# design.net
KiCad netlist of a schematic drawn in Altium Designer
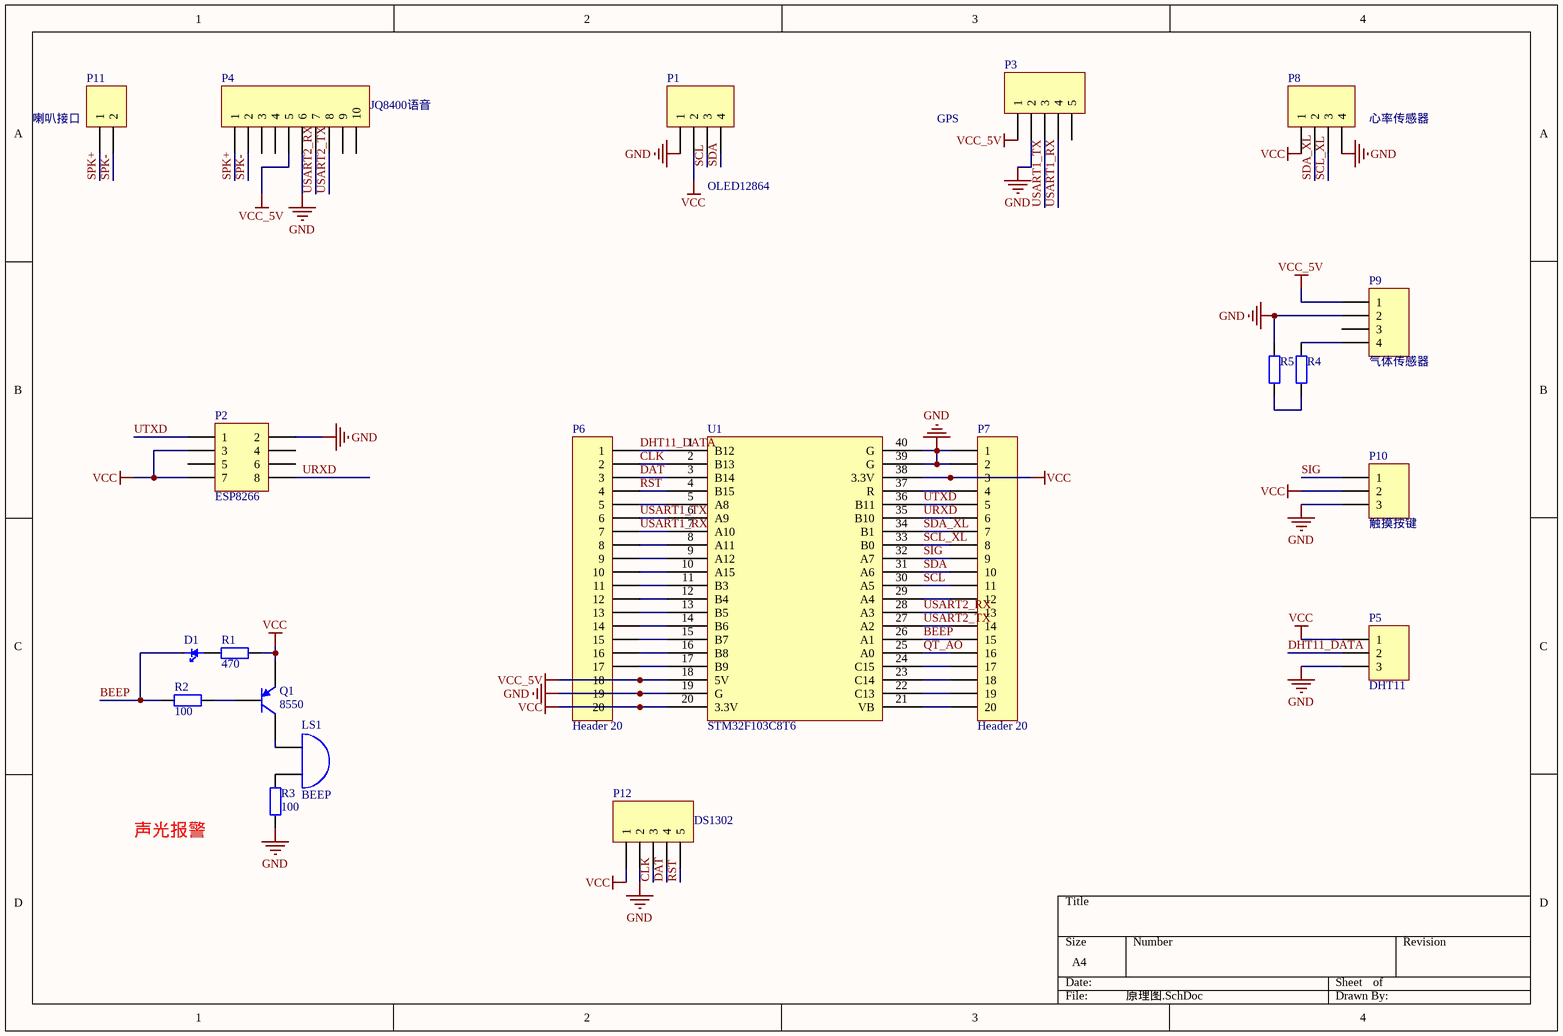
[diagram p0: 原理图.SchDoc]

(export (version "E")
  (design (tool "Eeschema 10.0.6"))
  (components
    (comp (ref "D1") (value "W") (footprint "LC-0805_LED_S1") (libsource (lib "个人") (part "LED")))
    (comp (ref "LS1")
      (value "BEEP")
      (footprint "HDR1X4")
      (description "Electrical Bell")
      (fields (field (name "PUBLISHER") "Altium Limited"))
      (libsource (lib "Miscellaneous Devices") (part "Bell"))
    )
    (comp (ref "P1")
      (value "OLED12864")
      (footprint "HDR1X4")
      (description "Header, 4-Pin")
      (fields (field (name "PUBLISHER") "Altium Limited"))
      (libsource (lib "Miscellaneous Connectors") (part "Header 4"))
    )
    (comp (ref "P2")
      (value "ESP8266")
      (footprint "HDR2X4")
      (description "Header, 4-Pin, Dual row")
      (fields (field (name "PUBLISHER") "Altium Limited"))
      (libsource (lib "Miscellaneous Connectors") (part "Header 4X2"))
    )
    (comp (ref "P3")
      (value "GPS")
      (footprint "HDR1X5")
      (description "Header, 5-Pin")
      (fields (field (name "PUBLISHER") "Altium Limited"))
      (libsource (lib "Miscellaneous Connectors") (part "Header 5"))
    )
    (comp (ref "P4")
      (value "JQ8400语音")
      (footprint "HDR1X10")
      (description "Header, 10-Pin")
      (fields (field (name "PUBLISHER") "Altium Limited"))
      (libsource (lib "Miscellaneous Connectors") (part "Header 10"))
    )
    (comp (ref "P5")
      (value "DHT11")
      (footprint "HDR1X3")
      (description "Header, 3-Pin")
      (fields (field (name "PUBLISHER") "Altium Limited"))
      (libsource (lib "Miscellaneous Connectors") (part "Header 3"))
    )
    (comp (ref "P6")
      (value "Header 20")
      (footprint "HDR1X20")
      (description "Header, 20-Pin")
      (fields (field (name "PUBLISHER") "Altium Limited"))
      (libsource (lib "") (part "Header 20_1"))
    )
    (comp (ref "P7")
      (value "Header 20")
      (footprint "HDR1X20")
      (description "Header, 20-Pin")
      (fields (field (name "PUBLISHER") "Altium Limited"))
      (libsource (lib "Miscellaneous Connectors") (part "Header 20"))
    )
    (comp (ref "P8")
      (value "心率传感器")
      (footprint "HDR1X4")
      (description "Header, 4-Pin")
      (fields (field (name "PUBLISHER") "Altium Limited"))
      (libsource (lib "Miscellaneous Connectors") (part "Header 4"))
    )
    (comp (ref "P9")
      (value "气体传感器")
      (footprint "HDR1X4")
      (description "Header, 4-Pin")
      (fields (field (name "PUBLISHER") "Altium Limited"))
      (libsource (lib "") (part "Header 4_1"))
    )
    (comp (ref "P10")
      (value "触摸按键")
      (footprint "HDR1X3")
      (description "Header, 3-Pin")
      (fields (field (name "PUBLISHER") "Altium Limited"))
      (libsource (lib "Miscellaneous Connectors") (part "Header 3"))
    )
    (comp (ref "P11")
      (value "喇叭接口")
      (footprint "HDR1X2")
      (description "Header, 2-Pin")
      (fields (field (name "PUBLISHER") "Altium Limited"))
      (libsource (lib "Miscellaneous Connectors") (part "Header 2"))
    )
    (comp (ref "P12")
      (value "DS1302")
      (footprint "HDR1X5")
      (description "Header, 5-Pin")
      (fields (field (name "PUBLISHER") "Altium Limited"))
      (libsource (lib "Miscellaneous Connectors") (part "Header 5"))
    )
    (comp (ref "Q1")
      (value "8550")
      (footprint "SOT-23 MOS")
      (description "PNP General Purpose Amplifier")
      (fields (field (name "PUBLISHER") "Altium Limited"))
      (libsource (lib "Miscellaneous Devices") (part "2N3906"))
    )
    (comp (ref "R1")
      (value "470")
      (footprint "0805")
      (description "Resistor")
      (fields (field (name "Comment") "Res2") (field (name "PUBLISHER") "Altium Limited"))
      (libsource (lib "Miscellaneous Devices") (part "Res2"))
    )
    (comp (ref "R2")
      (value "100")
      (footprint "0805")
      (description "Resistor")
      (fields (field (name "Comment") "Res2") (field (name "PUBLISHER") "Altium Limited"))
      (libsource (lib "Miscellaneous Devices") (part "Res2"))
    )
    (comp (ref "R3")
      (value "100")
      (footprint "0805")
      (description "Resistor")
      (fields (field (name "Comment") "Res2") (field (name "PUBLISHER") "Altium Limited"))
      (libsource (lib "") (part "Res2_2"))
    )
    (comp (ref "R4")
      (value "Res2")
      (footprint "0805")
      (description "Resistor")
      (fields (field (name "PUBLISHER") "Altium Limited"))
      (libsource (lib "") (part "Res2_1"))
    )
    (comp (ref "R5")
      (value "Res2")
      (footprint "0805")
      (description "Resistor")
      (fields (field (name "PUBLISHER") "Altium Limited"))
      (libsource (lib "") (part "Res2_1"))
    )
    (comp (ref "U1")
      (value "STM32F103C8T6")
      (footprint "STM32F103C8T6_HXB")
      (libsource (lib "stm32f103c8t6最小系统板") (part "Component_1"))
    )
  )
  (nets
    (net (code "1") (name "/BEEP") (class "Default")
      (node (ref "D1") (pin "K") (pinfunction "K_K") (pintype "passive"))
      (node (ref "P7") (pin "15") (pinfunction "15_15") (pintype "passive"))
      (node (ref "R2") (pin "2") (pinfunction "2_2") (pintype "passive"))
      (node (ref "U1") (pin "26") (pinfunction "A1_26") (pintype "passive"))
    )
    (net (code "2") (name "/CLK") (class "Default")
      (node (ref "P12") (pin "3") (pinfunction "3_3") (pintype "passive"))
      (node (ref "P6") (pin "2") (pinfunction "2_2") (pintype "passive"))
      (node (ref "U1") (pin "2") (pinfunction "B13_2") (pintype "passive"))
    )
    (net (code "3") (name "/DAT") (class "Default")
      (node (ref "P12") (pin "4") (pinfunction "4_4") (pintype "passive"))
      (node (ref "P6") (pin "3") (pinfunction "3_3") (pintype "passive"))
      (node (ref "U1") (pin "3") (pinfunction "B14_3") (pintype "passive"))
    )
    (net (code "4") (name "/DHT11_DATA") (class "Default")
      (node (ref "P5") (pin "2") (pinfunction "2_2") (pintype "passive"))
      (node (ref "P6") (pin "1") (pinfunction "1_1") (pintype "passive"))
      (node (ref "U1") (pin "1") (pinfunction "B12_1") (pintype "passive"))
    )
    (net (code "5") (name "/QT_AO") (class "Default")
      (node (ref "P7") (pin "16") (pinfunction "16_16") (pintype "passive"))
      (node (ref "U1") (pin "25") (pinfunction "A0_25") (pintype "passive"))
    )
    (net (code "6") (name "/RST") (class "Default")
      (node (ref "P12") (pin "5") (pinfunction "5_5") (pintype "passive"))
      (node (ref "P6") (pin "4") (pinfunction "4_4") (pintype "passive"))
      (node (ref "U1") (pin "4") (pinfunction "B15_4") (pintype "passive"))
    )
    (net (code "7") (name "/SCL") (class "Default")
      (node (ref "P1") (pin "3") (pinfunction "3_3") (pintype "passive"))
      (node (ref "P7") (pin "11") (pinfunction "11_11") (pintype "passive"))
      (node (ref "U1") (pin "30") (pinfunction "A5_30") (pintype "passive"))
    )
    (net (code "8") (name "/SCL_XL") (class "Default")
      (node (ref "P7") (pin "8") (pinfunction "8_8") (pintype "passive"))
      (node (ref "P8") (pin "3") (pinfunction "3_3") (pintype "passive"))
      (node (ref "U1") (pin "33") (pinfunction "B0_33") (pintype "passive"))
    )
    (net (code "9") (name "/SDA") (class "Default")
      (node (ref "P1") (pin "4") (pinfunction "4_4") (pintype "passive"))
      (node (ref "P7") (pin "10") (pinfunction "10_10") (pintype "passive"))
      (node (ref "U1") (pin "31") (pinfunction "A6_31") (pintype "passive"))
    )
    (net (code "10") (name "/SDA_XL") (class "Default")
      (node (ref "P7") (pin "7") (pinfunction "7_7") (pintype "passive"))
      (node (ref "P8") (pin "2") (pinfunction "2_2") (pintype "passive"))
      (node (ref "U1") (pin "34") (pinfunction "B1_34") (pintype "passive"))
    )
    (net (code "11") (name "/SIG") (class "Default")
      (node (ref "P10") (pin "1") (pinfunction "1_1") (pintype "passive"))
      (node (ref "P7") (pin "9") (pinfunction "9_9") (pintype "passive"))
      (node (ref "U1") (pin "32") (pinfunction "A7_32") (pintype "passive"))
    )
    (net (code "12") (name "/SPK+") (class "Default")
      (node (ref "P11") (pin "1") (pinfunction "1_1") (pintype "passive"))
      (node (ref "P4") (pin "1") (pinfunction "1_1") (pintype "passive"))
    )
    (net (code "13") (name "/SPK-") (class "Default")
      (node (ref "P11") (pin "2") (pinfunction "2_2") (pintype "passive"))
      (node (ref "P4") (pin "2") (pinfunction "2_2") (pintype "passive"))
    )
    (net (code "14") (name "/URXD") (class "Default")
      (node (ref "P2") (pin "8") (pinfunction "8_8") (pintype "passive"))
      (node (ref "P7") (pin "6") (pinfunction "6_6") (pintype "passive"))
      (node (ref "U1") (pin "35") (pinfunction "B10_35") (pintype "passive"))
    )
    (net (code "15") (name "/USART1_RX") (class "Default")
      (node (ref "P3") (pin "4") (pinfunction "4_4") (pintype "passive"))
      (node (ref "P6") (pin "7") (pinfunction "7_7") (pintype "passive"))
      (node (ref "U1") (pin "7") (pinfunction "A10_7") (pintype "passive"))
    )
    (net (code "16") (name "/USART1_TX") (class "Default")
      (node (ref "P3") (pin "3") (pinfunction "3_3") (pintype "passive"))
      (node (ref "P6") (pin "6") (pinfunction "6_6") (pintype "passive"))
      (node (ref "U1") (pin "6") (pinfunction "A9_6") (pintype "passive"))
    )
    (net (code "17") (name "/USART2_RX") (class "Default")
      (node (ref "P4") (pin "7") (pinfunction "7_7") (pintype "passive"))
      (node (ref "P7") (pin "13") (pinfunction "13_13") (pintype "passive"))
      (node (ref "U1") (pin "28") (pinfunction "A3_28") (pintype "passive"))
    )
    (net (code "18") (name "/USART2_TX") (class "Default")
      (node (ref "P4") (pin "8") (pinfunction "8_8") (pintype "passive"))
      (node (ref "P7") (pin "14") (pinfunction "14_14") (pintype "passive"))
      (node (ref "U1") (pin "27") (pinfunction "A2_27") (pintype "passive"))
    )
    (net (code "19") (name "/UTXD") (class "Default")
      (node (ref "P2") (pin "1") (pinfunction "1_1") (pintype "passive"))
      (node (ref "P7") (pin "5") (pinfunction "5_5") (pintype "passive"))
      (node (ref "U1") (pin "36") (pinfunction "B11_36") (pintype "passive"))
    )
    (net (code "20") (name "GND") (class "Default")
      (node (ref "P1") (pin "1") (pinfunction "1_1") (pintype "passive"))
      (node (ref "P10") (pin "3") (pinfunction "3_3") (pintype "passive"))
      (node (ref "P12") (pin "2") (pinfunction "2_2") (pintype "passive"))
      (node (ref "P2") (pin "2") (pinfunction "2_2") (pintype "passive"))
      (node (ref "P3") (pin "2") (pinfunction "2_2") (pintype "passive"))
      (node (ref "P4") (pin "6") (pinfunction "6_6") (pintype "passive"))
      (node (ref "P5") (pin "3") (pinfunction "3_3") (pintype "passive"))
      (node (ref "P6") (pin "19") (pinfunction "19_19") (pintype "passive"))
      (node (ref "P7") (pin "1") (pinfunction "1_1") (pintype "passive"))
      (node (ref "P7") (pin "2") (pinfunction "2_2") (pintype "passive"))
      (node (ref "P8") (pin "4") (pinfunction "4_4") (pintype "passive"))
      (node (ref "P9") (pin "2") (pinfunction "2_2") (pintype "passive"))
      (node (ref "R3") (pin "1") (pinfunction "1_1") (pintype "passive"))
      (node (ref "R5") (pin "1") (pinfunction "1_1") (pintype "passive"))
      (node (ref "U1") (pin "19") (pinfunction "G_19") (pintype "passive"))
      (node (ref "U1") (pin "39") (pinfunction "G_39") (pintype "passive"))
      (node (ref "U1") (pin "40") (pinfunction "G_40") (pintype "passive"))
    )
    (net (code "21") (name "Net-(D1-PadA)") (class "Default")
      (node (ref "D1") (pin "A") (pinfunction "A_A") (pintype "passive"))
      (node (ref "R1") (pin "2") (pinfunction "2_2") (pintype "passive"))
    )
    (net (code "22") (name "Net-(LS1-A)") (class "Default")
      (node (ref "LS1") (pin "1") (pinfunction "A_1") (pintype "passive"))
      (node (ref "Q1") (pin "3") (pinfunction "C_3") (pintype "passive"))
    )
    (net (code "23") (name "Net-(LS1-B)") (class "Default")
      (node (ref "LS1") (pin "2") (pinfunction "B_2") (pintype "passive"))
      (node (ref "R3") (pin "2") (pinfunction "2_2") (pintype "passive"))
    )
    (net (code "24") (name "Net-(P9-Pad4)") (class "Default")
      (node (ref "P9") (pin "4") (pinfunction "4_4") (pintype "passive"))
      (node (ref "R4") (pin "1") (pinfunction "1_1") (pintype "passive"))
    )
    (net (code "25") (name "Net-(Q1-B)") (class "Default")
      (node (ref "Q1") (pin "2") (pinfunction "B_2") (pintype "passive"))
      (node (ref "R2") (pin "1") (pinfunction "1_1") (pintype "passive"))
    )
    (net (code "26") (name "Net-(R4-Pad2)") (class "Default")
      (node (ref "R4") (pin "2") (pinfunction "2_2") (pintype "passive"))
      (node (ref "R5") (pin "2") (pinfunction "2_2") (pintype "passive"))
    )
    (net (code "27") (name "Net-(U1-A4)") (class "Default")
      (node (ref "P7") (pin "12") (pinfunction "12_12") (pintype "passive"))
      (node (ref "U1") (pin "29") (pinfunction "A4_29") (pintype "passive"))
    )
    (net (code "28") (name "Net-(U1-A8)") (class "Default")
      (node (ref "P6") (pin "5") (pinfunction "5_5") (pintype "passive"))
      (node (ref "U1") (pin "5") (pinfunction "A8_5") (pintype "passive"))
    )
    (net (code "29") (name "Net-(U1-A11)") (class "Default")
      (node (ref "P6") (pin "8") (pinfunction "8_8") (pintype "passive"))
      (node (ref "U1") (pin "8") (pinfunction "A11_8") (pintype "passive"))
    )
    (net (code "30") (name "Net-(U1-A12)") (class "Default")
      (node (ref "P6") (pin "9") (pinfunction "9_9") (pintype "passive"))
      (node (ref "U1") (pin "9") (pinfunction "A12_9") (pintype "passive"))
    )
    (net (code "31") (name "Net-(U1-A15)") (class "Default")
      (node (ref "P6") (pin "10") (pinfunction "10_10") (pintype "passive"))
      (node (ref "U1") (pin "10") (pinfunction "A15_10") (pintype "passive"))
    )
    (net (code "32") (name "Net-(U1-B3)") (class "Default")
      (node (ref "P6") (pin "11") (pinfunction "11_11") (pintype "passive"))
      (node (ref "U1") (pin "11") (pinfunction "B3_11") (pintype "passive"))
    )
    (net (code "33") (name "Net-(U1-B4)") (class "Default")
      (node (ref "P6") (pin "12") (pinfunction "12_12") (pintype "passive"))
      (node (ref "U1") (pin "12") (pinfunction "B4_12") (pintype "passive"))
    )
    (net (code "34") (name "Net-(U1-B5)") (class "Default")
      (node (ref "P6") (pin "13") (pinfunction "13_13") (pintype "passive"))
      (node (ref "U1") (pin "13") (pinfunction "B5_13") (pintype "passive"))
    )
    (net (code "35") (name "Net-(U1-B6)") (class "Default")
      (node (ref "P6") (pin "14") (pinfunction "14_14") (pintype "passive"))
      (node (ref "U1") (pin "14") (pinfunction "B6_14") (pintype "passive"))
    )
    (net (code "36") (name "Net-(U1-B7)") (class "Default")
      (node (ref "P6") (pin "15") (pinfunction "15_15") (pintype "passive"))
      (node (ref "U1") (pin "15") (pinfunction "B7_15") (pintype "passive"))
    )
    (net (code "37") (name "Net-(U1-B8)") (class "Default")
      (node (ref "P6") (pin "16") (pinfunction "16_16") (pintype "passive"))
      (node (ref "U1") (pin "16") (pinfunction "B8_16") (pintype "passive"))
    )
    (net (code "38") (name "Net-(U1-B9)") (class "Default")
      (node (ref "P6") (pin "17") (pinfunction "17_17") (pintype "passive"))
      (node (ref "U1") (pin "17") (pinfunction "B9_17") (pintype "passive"))
    )
    (net (code "39") (name "Net-(U1-C13)") (class "Default")
      (node (ref "P7") (pin "19") (pinfunction "19_19") (pintype "passive"))
      (node (ref "U1") (pin "22") (pinfunction "C13_22") (pintype "passive"))
    )
    (net (code "40") (name "Net-(U1-C14)") (class "Default")
      (node (ref "P7") (pin "18") (pinfunction "18_18") (pintype "passive"))
      (node (ref "U1") (pin "23") (pinfunction "C14_23") (pintype "passive"))
    )
    (net (code "41") (name "Net-(U1-C15)") (class "Default")
      (node (ref "P7") (pin "17") (pinfunction "17_17") (pintype "passive"))
      (node (ref "U1") (pin "24") (pinfunction "C15_24") (pintype "passive"))
    )
    (net (code "42") (name "Net-(U1-R)") (class "Default")
      (node (ref "P7") (pin "4") (pinfunction "4_4") (pintype "passive"))
      (node (ref "U1") (pin "37") (pinfunction "R_37") (pintype "passive"))
    )
    (net (code "43") (name "Net-(U1-VB)") (class "Default")
      (node (ref "P7") (pin "20") (pinfunction "20_20") (pintype "passive"))
      (node (ref "U1") (pin "21") (pinfunction "VB_21") (pintype "passive"))
    )
    (net (code "44") (name "VCC") (class "Default")
      (node (ref "P1") (pin "2") (pinfunction "2_2") (pintype "passive"))
      (node (ref "P10") (pin "2") (pinfunction "2_2") (pintype "passive"))
      (node (ref "P12") (pin "1") (pinfunction "1_1") (pintype "passive"))
      (node (ref "P2") (pin "3") (pinfunction "3_3") (pintype "passive"))
      (node (ref "P2") (pin "7") (pinfunction "7_7") (pintype "passive"))
      (node (ref "P5") (pin "1") (pinfunction "1_1") (pintype "passive"))
      (node (ref "P6") (pin "20") (pinfunction "20_20") (pintype "passive"))
      (node (ref "P7") (pin "3") (pinfunction "3_3") (pintype "passive"))
      (node (ref "P8") (pin "1") (pinfunction "1_1") (pintype "passive"))
      (node (ref "Q1") (pin "1") (pinfunction "E_1") (pintype "passive"))
      (node (ref "R1") (pin "1") (pinfunction "1_1") (pintype "passive"))
      (node (ref "U1") (pin "20") (pinfunction "3.3V_20") (pintype "passive"))
      (node (ref "U1") (pin "38") (pinfunction "3.3V_38") (pintype "passive"))
    )
    (net (code "45") (name "VCC_5V") (class "Default")
      (node (ref "P3") (pin "1") (pinfunction "1_1") (pintype "passive"))
      (node (ref "P4") (pin "5") (pinfunction "5_5") (pintype "passive"))
      (node (ref "P6") (pin "18") (pinfunction "18_18") (pintype "passive"))
      (node (ref "P9") (pin "1") (pinfunction "1_1") (pintype "passive"))
      (node (ref "U1") (pin "18") (pinfunction "5V_18") (pintype "passive"))
    )
    (net (code "46") (name "unconnected-(P2-Pad4)") (class "Default")
      (node (ref "P2") (pin "4") (pinfunction "4_4") (pintype "passive"))
    )
    (net (code "47") (name "unconnected-(P2-Pad5)") (class "Default")
      (node (ref "P2") (pin "5") (pinfunction "5_5") (pintype "passive"))
    )
    (net (code "48") (name "unconnected-(P2-Pad6)") (class "Default")
      (node (ref "P2") (pin "6") (pinfunction "6_6") (pintype "passive"))
    )
    (net (code "49") (name "unconnected-(P3-Pad5)") (class "Default")
      (node (ref "P3") (pin "5") (pinfunction "5_5") (pintype "passive"))
    )
    (net (code "50") (name "unconnected-(P4-Pad3)") (class "Default")
      (node (ref "P4") (pin "3") (pinfunction "3_3") (pintype "passive"))
    )
    (net (code "51") (name "unconnected-(P4-Pad4)") (class "Default")
      (node (ref "P4") (pin "4") (pinfunction "4_4") (pintype "passive"))
    )
    (net (code "52") (name "unconnected-(P4-Pad9)") (class "Default")
      (node (ref "P4") (pin "9") (pinfunction "9_9") (pintype "passive"))
    )
    (net (code "53") (name "unconnected-(P4-Pad10)") (class "Default")
      (node (ref "P4") (pin "10") (pinfunction "10_10") (pintype "passive"))
    )
    (net (code "54") (name "unconnected-(P9-Pad3)") (class "Default")
      (node (ref "P9") (pin "3") (pinfunction "3_3") (pintype "passive"))
    )
  )
)
